# lupa-breakout.net
KiCad netlist of a schematic drawn in EAGLE
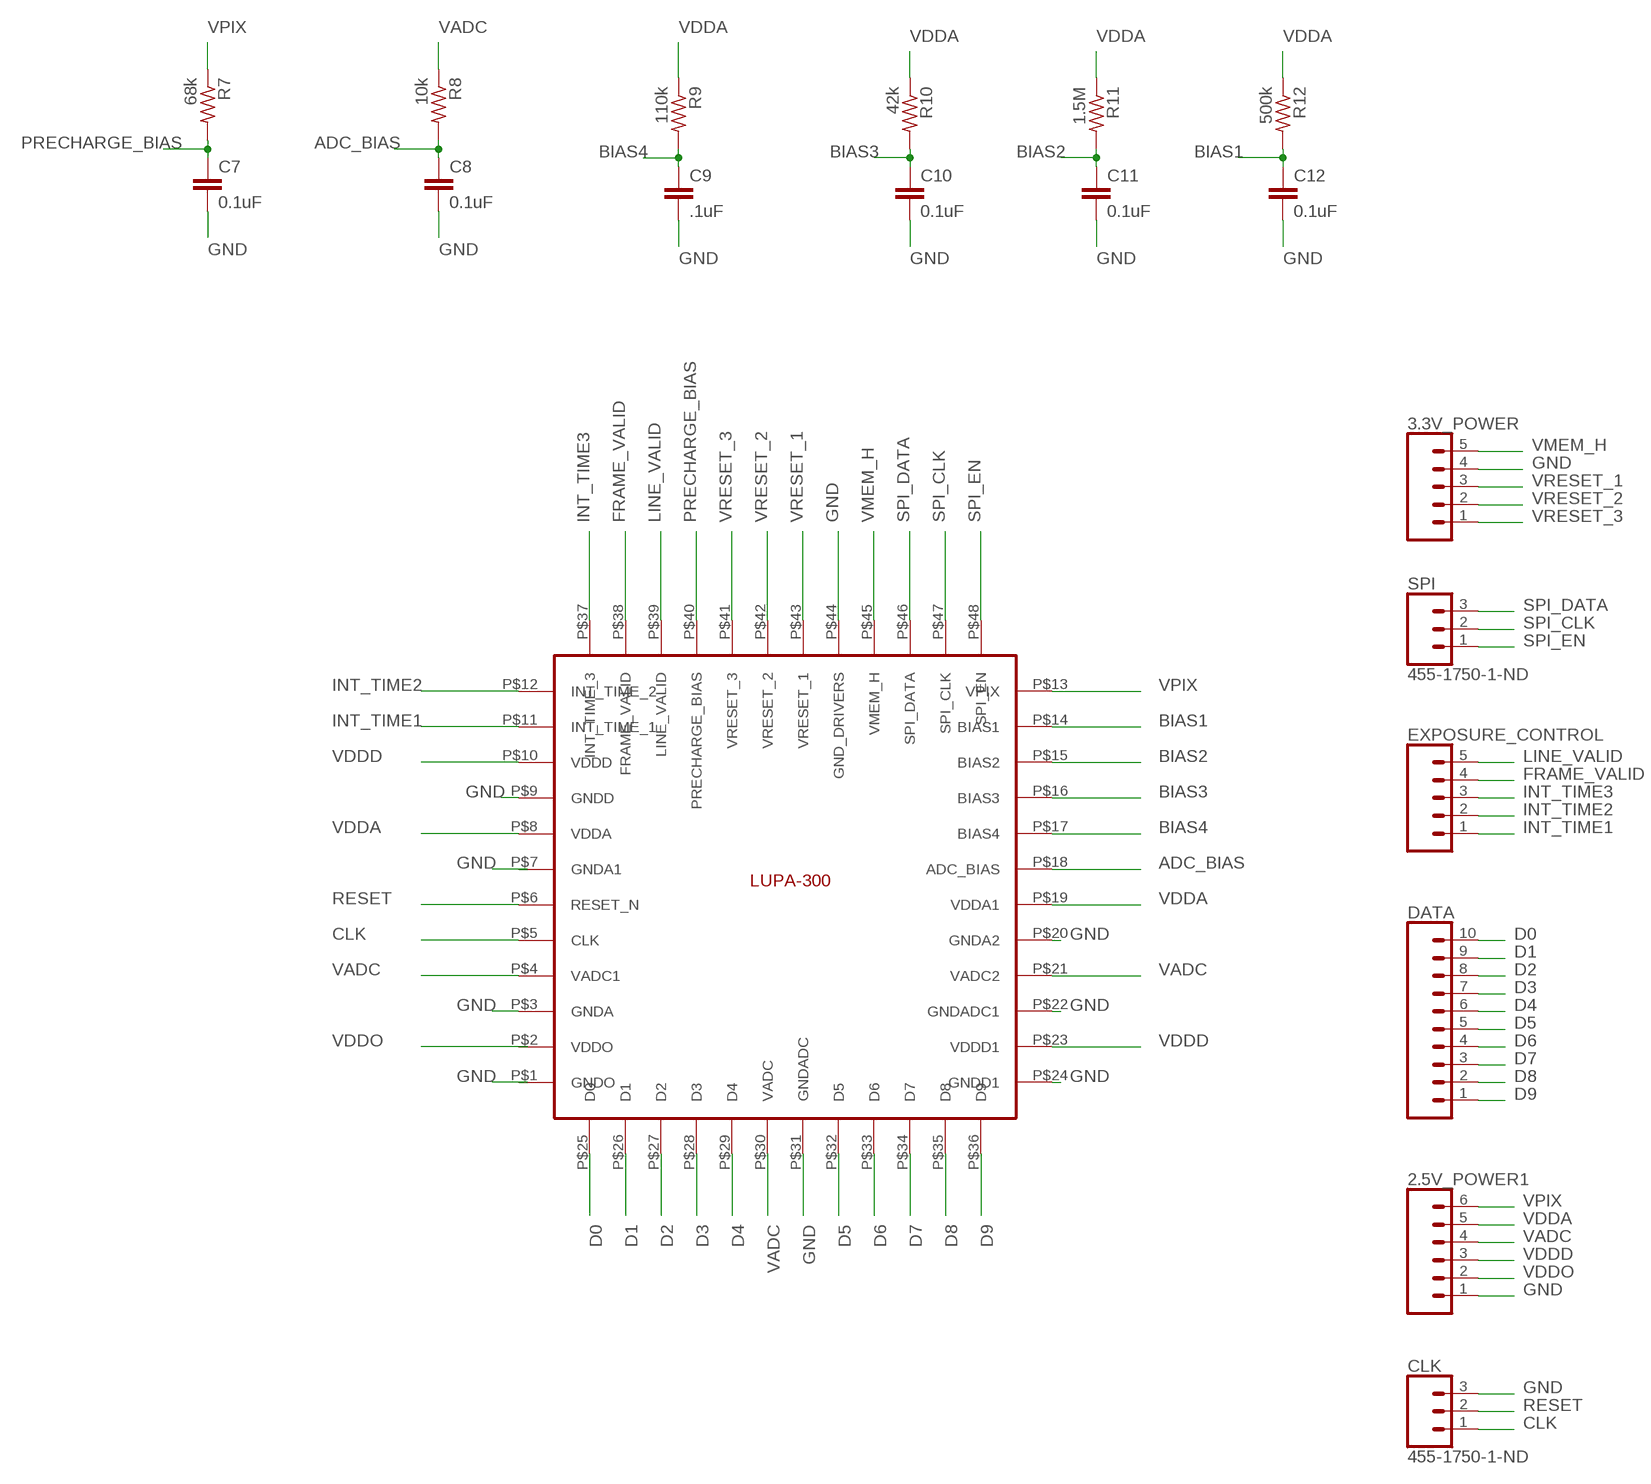
[diagram p0: schematic, sheet 1]

(export (version "E")
  (design (tool "Eeschema 10.0.6"))
  (components
    (comp (ref "2.5V_POWER1")
      (value "CONN_06SILK_FEMALE_PTH")
      (footprint "eagle-import:1X06")
      (libsource (lib "eagle-import") (part "CONN_06SILK_FEMALE_PTH"))
    )
    (comp (ref "3.3V_POWER")
      (value "CONN_05")
      (footprint "eagle-import:1X05")
      (libsource (lib "eagle-import") (part "CONN_05"))
    )
    (comp (ref "C7")
      (value "0.1uF")
      (footprint "eagle-import:C1206")
      (libsource (lib "eagle-import") (part "C-EUC1206"))
    )
    (comp (ref "C8")
      (value "0.1uF")
      (footprint "eagle-import:C1206")
      (libsource (lib "eagle-import") (part "C-EUC1206"))
    )
    (comp (ref "C9")
      (value ".1uF")
      (footprint "eagle-import:C1206")
      (libsource (lib "eagle-import") (part "C-EUC1206"))
    )
    (comp (ref "C10")
      (value "0.1uF")
      (footprint "eagle-import:C1206")
      (libsource (lib "eagle-import") (part "C-EUC1206"))
    )
    (comp (ref "C11")
      (value "0.1uF")
      (footprint "eagle-import:C1206")
      (libsource (lib "eagle-import") (part "C-EUC1206"))
    )
    (comp (ref "C12")
      (value "0.1uF")
      (footprint "eagle-import:C1206")
      (libsource (lib "eagle-import") (part "C-EUC1206"))
    )
    (comp (ref "CLK")
      (value "455-1750-1-ND")
      (footprint "eagle-import:1X03")
      (libsource (lib "eagle-import") (part "CONN_03"))
    )
    (comp (ref "DATA")
      (value "CONN_10\"")
      (footprint "eagle-import:1X10")
      (libsource (lib "eagle-import") (part "CONN_10{dblquote}"))
    )
    (comp (ref "EXPOSURE_CONTROL")
      (value "CONN_05")
      (footprint "eagle-import:1X05")
      (libsource (lib "eagle-import") (part "CONN_05"))
    )
    (comp (ref "R7")
      (value "68k")
      (footprint "eagle-import:M1206")
      (libsource (lib "eagle-import") (part "R-US_M1206"))
    )
    (comp (ref "R8")
      (value "10k")
      (footprint "eagle-import:M1206")
      (libsource (lib "eagle-import") (part "R-US_M1206"))
    )
    (comp (ref "R9")
      (value "110k")
      (footprint "eagle-import:M1206")
      (libsource (lib "eagle-import") (part "R-US_M1206"))
    )
    (comp (ref "R10")
      (value "42k")
      (footprint "eagle-import:M1206")
      (libsource (lib "eagle-import") (part "R-US_M1206"))
    )
    (comp (ref "R11")
      (value "1.5M")
      (footprint "eagle-import:M1206")
      (libsource (lib "eagle-import") (part "R-US_M1206"))
    )
    (comp (ref "R12")
      (value "500k")
      (footprint "eagle-import:M1206")
      (libsource (lib "eagle-import") (part "R-US_M1206"))
    )
    (comp (ref "SPI")
      (value "455-1750-1-ND")
      (footprint "eagle-import:1X03")
      (libsource (lib "eagle-import") (part "CONN_03"))
    )
    (comp (ref "U$1")
      (value "LUPA300")
      (footprint "eagle-import:LUPA300")
      (libsource (lib "eagle-import") (part "LUPA300"))
    )
  )
  (nets
    (net (code "1") (name "/ADC_BIAS") (class "Default")
      (node (ref "C8") (pin "1") (pinfunction "1_1") (pintype "passive"))
      (node (ref "R8") (pin "2") (pinfunction "2_2") (pintype "passive"))
      (node (ref "U$1") (pin "P$18") (pinfunction "ADC_BIAS_P$18") (pintype "bidirectional"))
    )
    (net (code "2") (name "/BIAS1") (class "Default")
      (node (ref "C12") (pin "1") (pinfunction "1_1") (pintype "passive"))
      (node (ref "R12") (pin "2") (pinfunction "2_2") (pintype "passive"))
      (node (ref "U$1") (pin "P$14") (pinfunction "BIAS1_P$14") (pintype "bidirectional"))
    )
    (net (code "3") (name "/BIAS2") (class "Default")
      (node (ref "C11") (pin "1") (pinfunction "1_1") (pintype "passive"))
      (node (ref "R11") (pin "2") (pinfunction "2_2") (pintype "passive"))
      (node (ref "U$1") (pin "P$15") (pinfunction "BIAS2_P$15") (pintype "bidirectional"))
    )
    (net (code "4") (name "/BIAS3") (class "Default")
      (node (ref "C10") (pin "1") (pinfunction "1_1") (pintype "passive"))
      (node (ref "R10") (pin "2") (pinfunction "2_2") (pintype "passive"))
      (node (ref "U$1") (pin "P$16") (pinfunction "BIAS3_P$16") (pintype "bidirectional"))
    )
    (net (code "5") (name "/BIAS4") (class "Default")
      (node (ref "C9") (pin "1") (pinfunction "1_1") (pintype "passive"))
      (node (ref "R9") (pin "2") (pinfunction "2_2") (pintype "passive"))
      (node (ref "U$1") (pin "P$17") (pinfunction "BIAS4_P$17") (pintype "bidirectional"))
    )
    (net (code "6") (name "/CLK") (class "Default")
      (node (ref "CLK") (pin "1") (pinfunction "1_1") (pintype "passive"))
      (node (ref "U$1") (pin "P$5") (pinfunction "CLK_P$5") (pintype "bidirectional"))
    )
    (net (code "7") (name "/D0") (class "Default")
      (node (ref "DATA") (pin "10") (pinfunction "10_10") (pintype "passive"))
      (node (ref "U$1") (pin "P$25") (pinfunction "D0_P$25") (pintype "bidirectional"))
    )
    (net (code "8") (name "/D1") (class "Default")
      (node (ref "DATA") (pin "9") (pinfunction "9_9") (pintype "passive"))
      (node (ref "U$1") (pin "P$26") (pinfunction "D1_P$26") (pintype "bidirectional"))
    )
    (net (code "9") (name "/D2") (class "Default")
      (node (ref "DATA") (pin "8") (pinfunction "8_8") (pintype "passive"))
      (node (ref "U$1") (pin "P$27") (pinfunction "D2_P$27") (pintype "bidirectional"))
    )
    (net (code "10") (name "/D3") (class "Default")
      (node (ref "DATA") (pin "7") (pinfunction "7_7") (pintype "passive"))
      (node (ref "U$1") (pin "P$28") (pinfunction "D3_P$28") (pintype "bidirectional"))
    )
    (net (code "11") (name "/D4") (class "Default")
      (node (ref "DATA") (pin "6") (pinfunction "6_6") (pintype "passive"))
      (node (ref "U$1") (pin "P$29") (pinfunction "D4_P$29") (pintype "bidirectional"))
    )
    (net (code "12") (name "/D5") (class "Default")
      (node (ref "DATA") (pin "5") (pinfunction "5_5") (pintype "passive"))
      (node (ref "U$1") (pin "P$32") (pinfunction "D5_P$32") (pintype "bidirectional"))
    )
    (net (code "13") (name "/D6") (class "Default")
      (node (ref "DATA") (pin "4") (pinfunction "4_4") (pintype "passive"))
      (node (ref "U$1") (pin "P$33") (pinfunction "D6_P$33") (pintype "bidirectional"))
    )
    (net (code "14") (name "/D7") (class "Default")
      (node (ref "DATA") (pin "3") (pinfunction "3_3") (pintype "passive"))
      (node (ref "U$1") (pin "P$34") (pinfunction "D7_P$34") (pintype "bidirectional"))
    )
    (net (code "15") (name "/D8") (class "Default")
      (node (ref "DATA") (pin "2") (pinfunction "2_2") (pintype "passive"))
      (node (ref "U$1") (pin "P$35") (pinfunction "D8_P$35") (pintype "bidirectional"))
    )
    (net (code "16") (name "/D9") (class "Default")
      (node (ref "DATA") (pin "1") (pinfunction "1_1") (pintype "passive"))
      (node (ref "U$1") (pin "P$36") (pinfunction "D9_P$36") (pintype "bidirectional"))
    )
    (net (code "17") (name "/FRAME_VALID") (class "Default")
      (node (ref "EXPOSURE_CONTROL") (pin "4") (pinfunction "4_4") (pintype "passive"))
      (node (ref "U$1") (pin "P$38") (pinfunction "FRAME_VALID_P$38") (pintype "bidirectional"))
    )
    (net (code "18") (name "/GND") (class "Default")
      (node (ref "2.5V_POWER1") (pin "1") (pinfunction "1_1") (pintype "passive"))
      (node (ref "3.3V_POWER") (pin "4") (pinfunction "4_4") (pintype "passive"))
      (node (ref "C10") (pin "2") (pinfunction "2_2") (pintype "passive"))
      (node (ref "C11") (pin "2") (pinfunction "2_2") (pintype "passive"))
      (node (ref "C12") (pin "2") (pinfunction "2_2") (pintype "passive"))
      (node (ref "C7") (pin "2") (pinfunction "2_2") (pintype "passive"))
      (node (ref "C8") (pin "2") (pinfunction "2_2") (pintype "passive"))
      (node (ref "C9") (pin "2") (pinfunction "2_2") (pintype "passive"))
      (node (ref "CLK") (pin "3") (pinfunction "3_3") (pintype "passive"))
      (node (ref "U$1") (pin "P$1") (pinfunction "GNDO_P$1") (pintype "bidirectional"))
      (node (ref "U$1") (pin "P$20") (pinfunction "GNDA2_P$20") (pintype "bidirectional"))
      (node (ref "U$1") (pin "P$22") (pinfunction "GNDADC1_P$22") (pintype "bidirectional"))
      (node (ref "U$1") (pin "P$24") (pinfunction "GNDD1_P$24") (pintype "bidirectional"))
      (node (ref "U$1") (pin "P$3") (pinfunction "GNDA_P$3") (pintype "bidirectional"))
      (node (ref "U$1") (pin "P$31") (pinfunction "GNDADC_P$31") (pintype "bidirectional"))
      (node (ref "U$1") (pin "P$44") (pinfunction "GND_DRIVERS_P$44") (pintype "bidirectional"))
      (node (ref "U$1") (pin "P$9") (pinfunction "GNDD_P$9") (pintype "bidirectional"))
    )
    (net (code "19") (name "/INT_TIME1") (class "Default")
      (node (ref "EXPOSURE_CONTROL") (pin "1") (pinfunction "1_1") (pintype "passive"))
      (node (ref "U$1") (pin "P$11") (pinfunction "INT_TIME_1_P$11") (pintype "bidirectional"))
    )
    (net (code "20") (name "/INT_TIME2") (class "Default")
      (node (ref "EXPOSURE_CONTROL") (pin "2") (pinfunction "2_2") (pintype "passive"))
      (node (ref "U$1") (pin "P$12") (pinfunction "INT_TIME_2_P$12") (pintype "bidirectional"))
    )
    (net (code "21") (name "/INT_TIME3") (class "Default")
      (node (ref "EXPOSURE_CONTROL") (pin "3") (pinfunction "3_3") (pintype "passive"))
      (node (ref "U$1") (pin "P$37") (pinfunction "INT_TIME_3_P$37") (pintype "bidirectional"))
    )
    (net (code "22") (name "/LINE_VALID") (class "Default")
      (node (ref "EXPOSURE_CONTROL") (pin "5") (pinfunction "5_5") (pintype "passive"))
      (node (ref "U$1") (pin "P$39") (pinfunction "LINE_VALID_P$39") (pintype "bidirectional"))
    )
    (net (code "23") (name "/PRECHARGE_BIAS") (class "Default")
      (node (ref "C7") (pin "1") (pinfunction "1_1") (pintype "passive"))
      (node (ref "R7") (pin "2") (pinfunction "2_2") (pintype "passive"))
      (node (ref "U$1") (pin "P$40") (pinfunction "PRECHARGE_BIAS_P$40") (pintype "bidirectional"))
    )
    (net (code "24") (name "/RESET") (class "Default")
      (node (ref "CLK") (pin "2") (pinfunction "2_2") (pintype "passive"))
      (node (ref "U$1") (pin "P$6") (pinfunction "RESET_N_P$6") (pintype "bidirectional"))
    )
    (net (code "25") (name "/SPI_CLK") (class "Default")
      (node (ref "SPI") (pin "2") (pinfunction "2_2") (pintype "passive"))
      (node (ref "U$1") (pin "P$47") (pinfunction "SPI_CLK_P$47") (pintype "bidirectional"))
    )
    (net (code "26") (name "/SPI_DATA") (class "Default")
      (node (ref "SPI") (pin "3") (pinfunction "3_3") (pintype "passive"))
      (node (ref "U$1") (pin "P$46") (pinfunction "SPI_DATA_P$46") (pintype "bidirectional"))
    )
    (net (code "27") (name "/SPI_EN") (class "Default")
      (node (ref "SPI") (pin "1") (pinfunction "1_1") (pintype "passive"))
      (node (ref "U$1") (pin "P$48") (pinfunction "SPI_EN_P$48") (pintype "bidirectional"))
    )
    (net (code "28") (name "/VADC") (class "Default")
      (node (ref "2.5V_POWER1") (pin "4") (pinfunction "4_4") (pintype "passive"))
      (node (ref "R8") (pin "1") (pinfunction "1_1") (pintype "passive"))
      (node (ref "U$1") (pin "P$21") (pinfunction "VADC2_P$21") (pintype "bidirectional"))
      (node (ref "U$1") (pin "P$30") (pinfunction "VADC_P$30") (pintype "bidirectional"))
      (node (ref "U$1") (pin "P$4") (pinfunction "VADC1_P$4") (pintype "bidirectional"))
    )
    (net (code "29") (name "/VDDA") (class "Default")
      (node (ref "2.5V_POWER1") (pin "5") (pinfunction "5_5") (pintype "passive"))
      (node (ref "R10") (pin "1") (pinfunction "1_1") (pintype "passive"))
      (node (ref "R11") (pin "1") (pinfunction "1_1") (pintype "passive"))
      (node (ref "R12") (pin "1") (pinfunction "1_1") (pintype "passive"))
      (node (ref "R9") (pin "1") (pinfunction "1_1") (pintype "passive"))
      (node (ref "U$1") (pin "P$19") (pinfunction "VDDA1_P$19") (pintype "bidirectional"))
      (node (ref "U$1") (pin "P$8") (pinfunction "VDDA_P$8") (pintype "bidirectional"))
    )
    (net (code "30") (name "/VDDD") (class "Default")
      (node (ref "2.5V_POWER1") (pin "3") (pinfunction "3_3") (pintype "passive"))
      (node (ref "U$1") (pin "P$10") (pinfunction "VDDD_P$10") (pintype "bidirectional"))
      (node (ref "U$1") (pin "P$23") (pinfunction "VDDD1_P$23") (pintype "bidirectional"))
    )
    (net (code "31") (name "/VDDO") (class "Default")
      (node (ref "2.5V_POWER1") (pin "2") (pinfunction "2_2") (pintype "passive"))
      (node (ref "U$1") (pin "P$2") (pinfunction "VDDO_P$2") (pintype "bidirectional"))
    )
    (net (code "32") (name "/VMEM_H") (class "Default")
      (node (ref "3.3V_POWER") (pin "5") (pinfunction "5_5") (pintype "passive"))
      (node (ref "U$1") (pin "P$45") (pinfunction "VMEM_H_P$45") (pintype "bidirectional"))
    )
    (net (code "33") (name "/VPIX") (class "Default")
      (node (ref "2.5V_POWER1") (pin "6") (pinfunction "6_6") (pintype "passive"))
      (node (ref "R7") (pin "1") (pinfunction "1_1") (pintype "passive"))
      (node (ref "U$1") (pin "P$13") (pinfunction "VPIX_P$13") (pintype "bidirectional"))
    )
    (net (code "34") (name "/VRESET_1") (class "Default")
      (node (ref "3.3V_POWER") (pin "3") (pinfunction "3_3") (pintype "passive"))
      (node (ref "U$1") (pin "P$43") (pinfunction "VRESET_1_P$43") (pintype "bidirectional"))
    )
    (net (code "35") (name "/VRESET_2") (class "Default")
      (node (ref "3.3V_POWER") (pin "2") (pinfunction "2_2") (pintype "passive"))
      (node (ref "U$1") (pin "P$42") (pinfunction "VRESET_2_P$42") (pintype "bidirectional"))
    )
    (net (code "36") (name "/VRESET_3") (class "Default")
      (node (ref "3.3V_POWER") (pin "1") (pinfunction "1_1") (pintype "passive"))
      (node (ref "U$1") (pin "P$41") (pinfunction "VRESET_3_P$41") (pintype "bidirectional"))
    )
    (net (code "37") (name "unconnected-(U$1-GNDA1-PadP$7)") (class "Default")
      (node (ref "U$1") (pin "P$7") (pinfunction "GNDA1_P$7") (pintype "bidirectional"))
    )
  )
)
